# ads-b.net
KiCad netlist of a schematic drawn in EAGLE
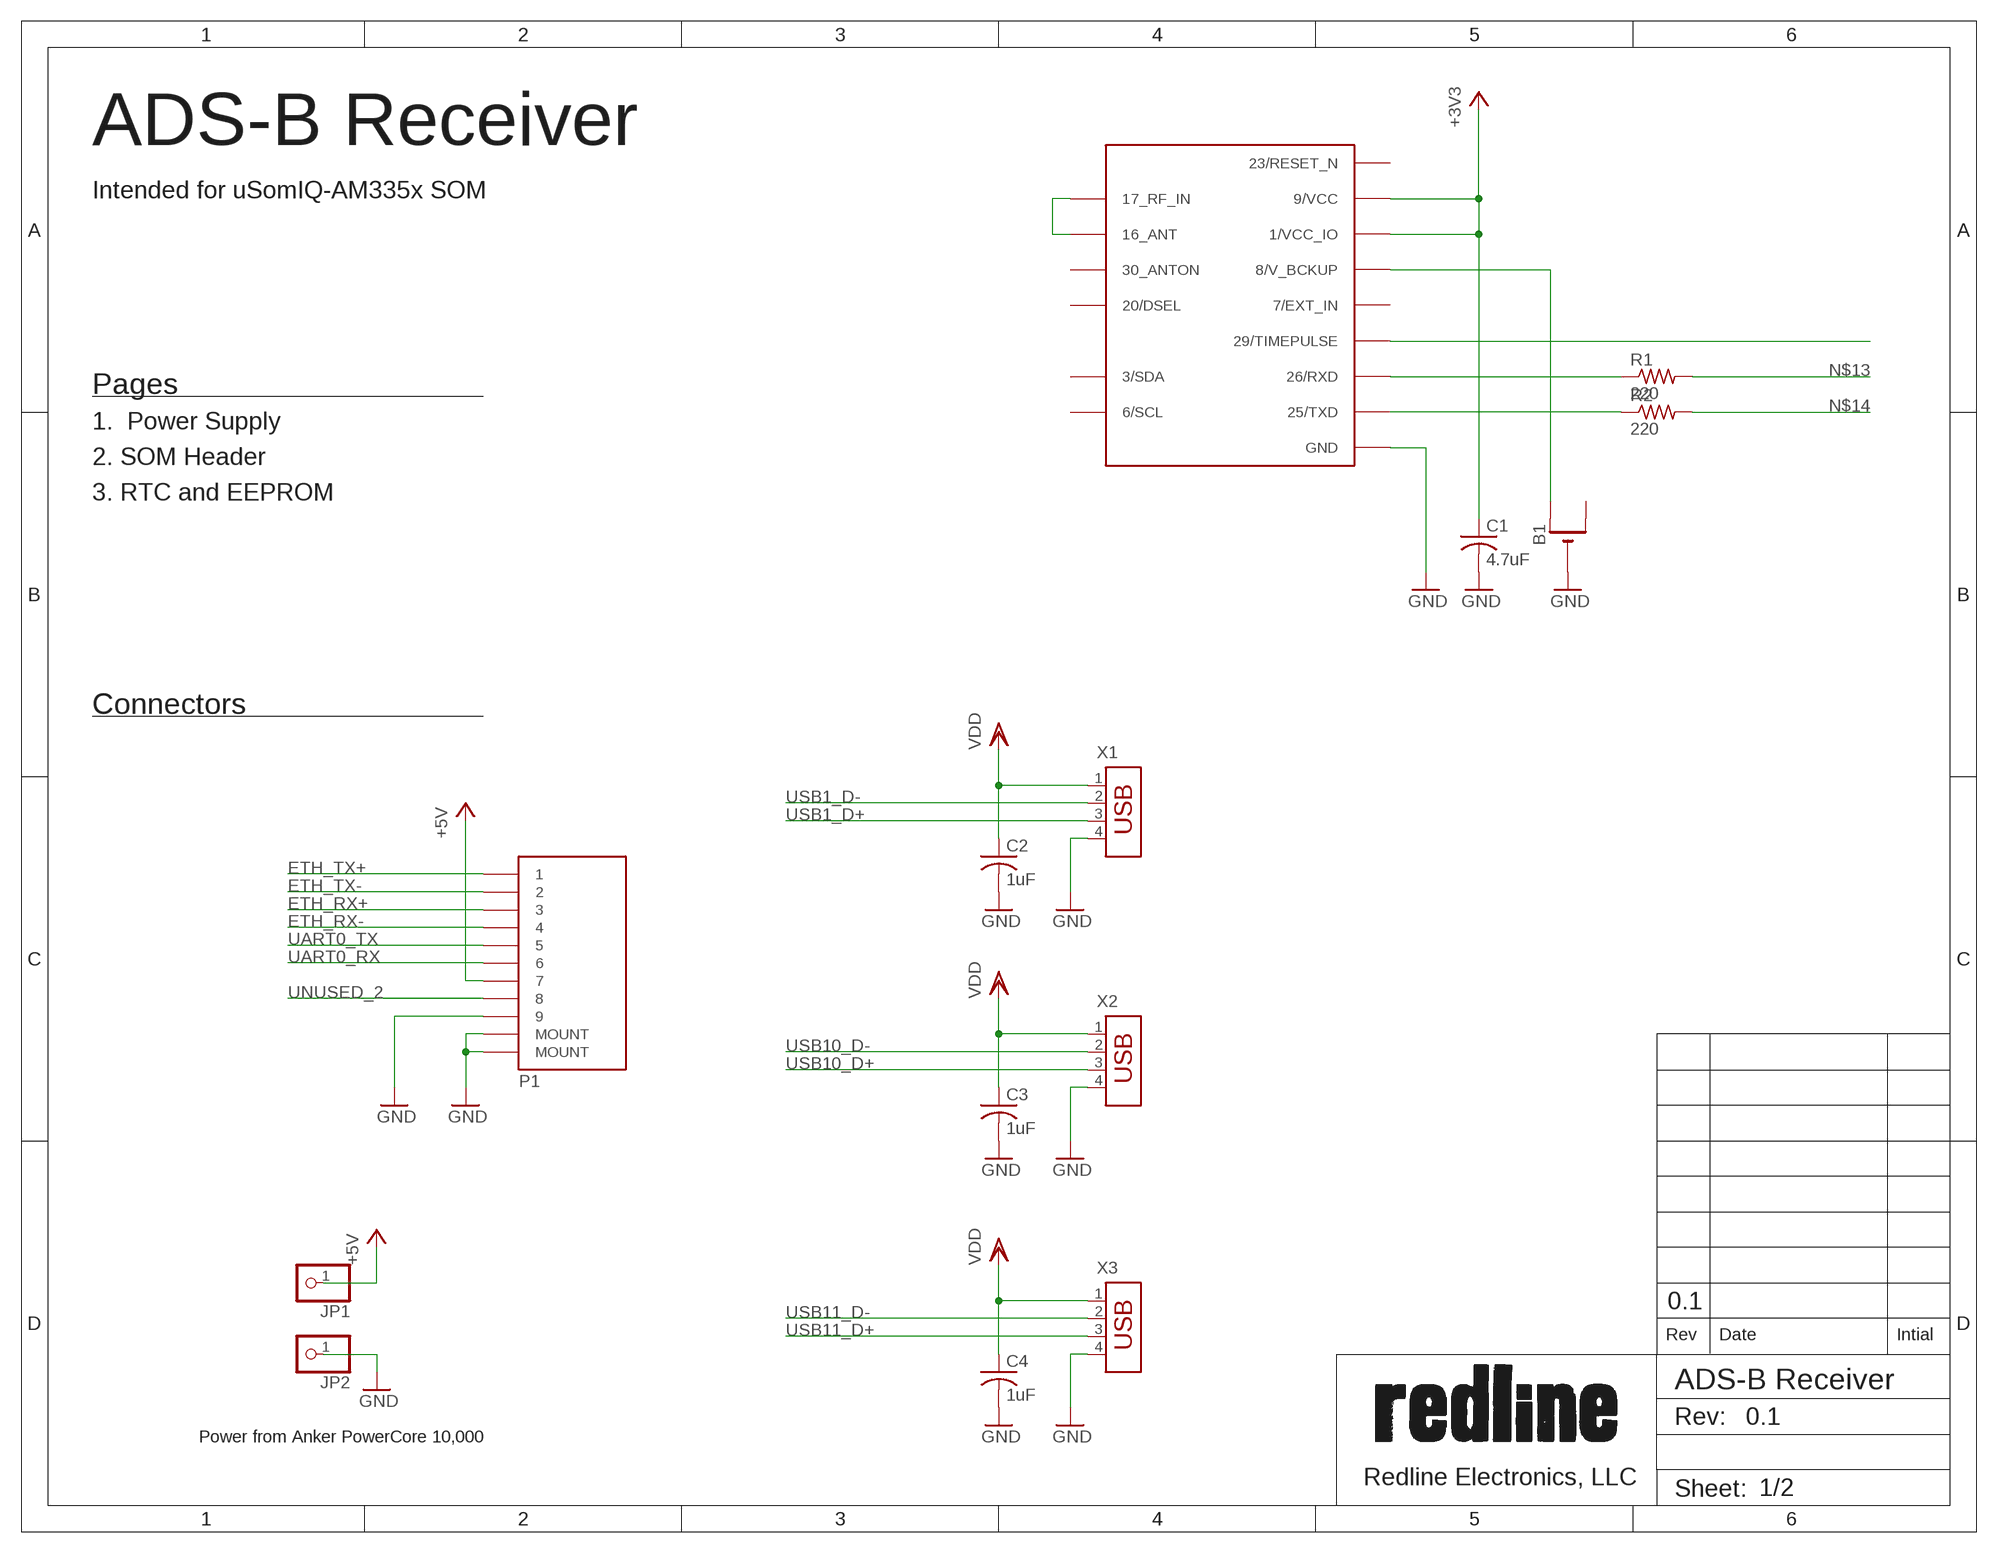
[diagram p0: schematic, sheet 1]
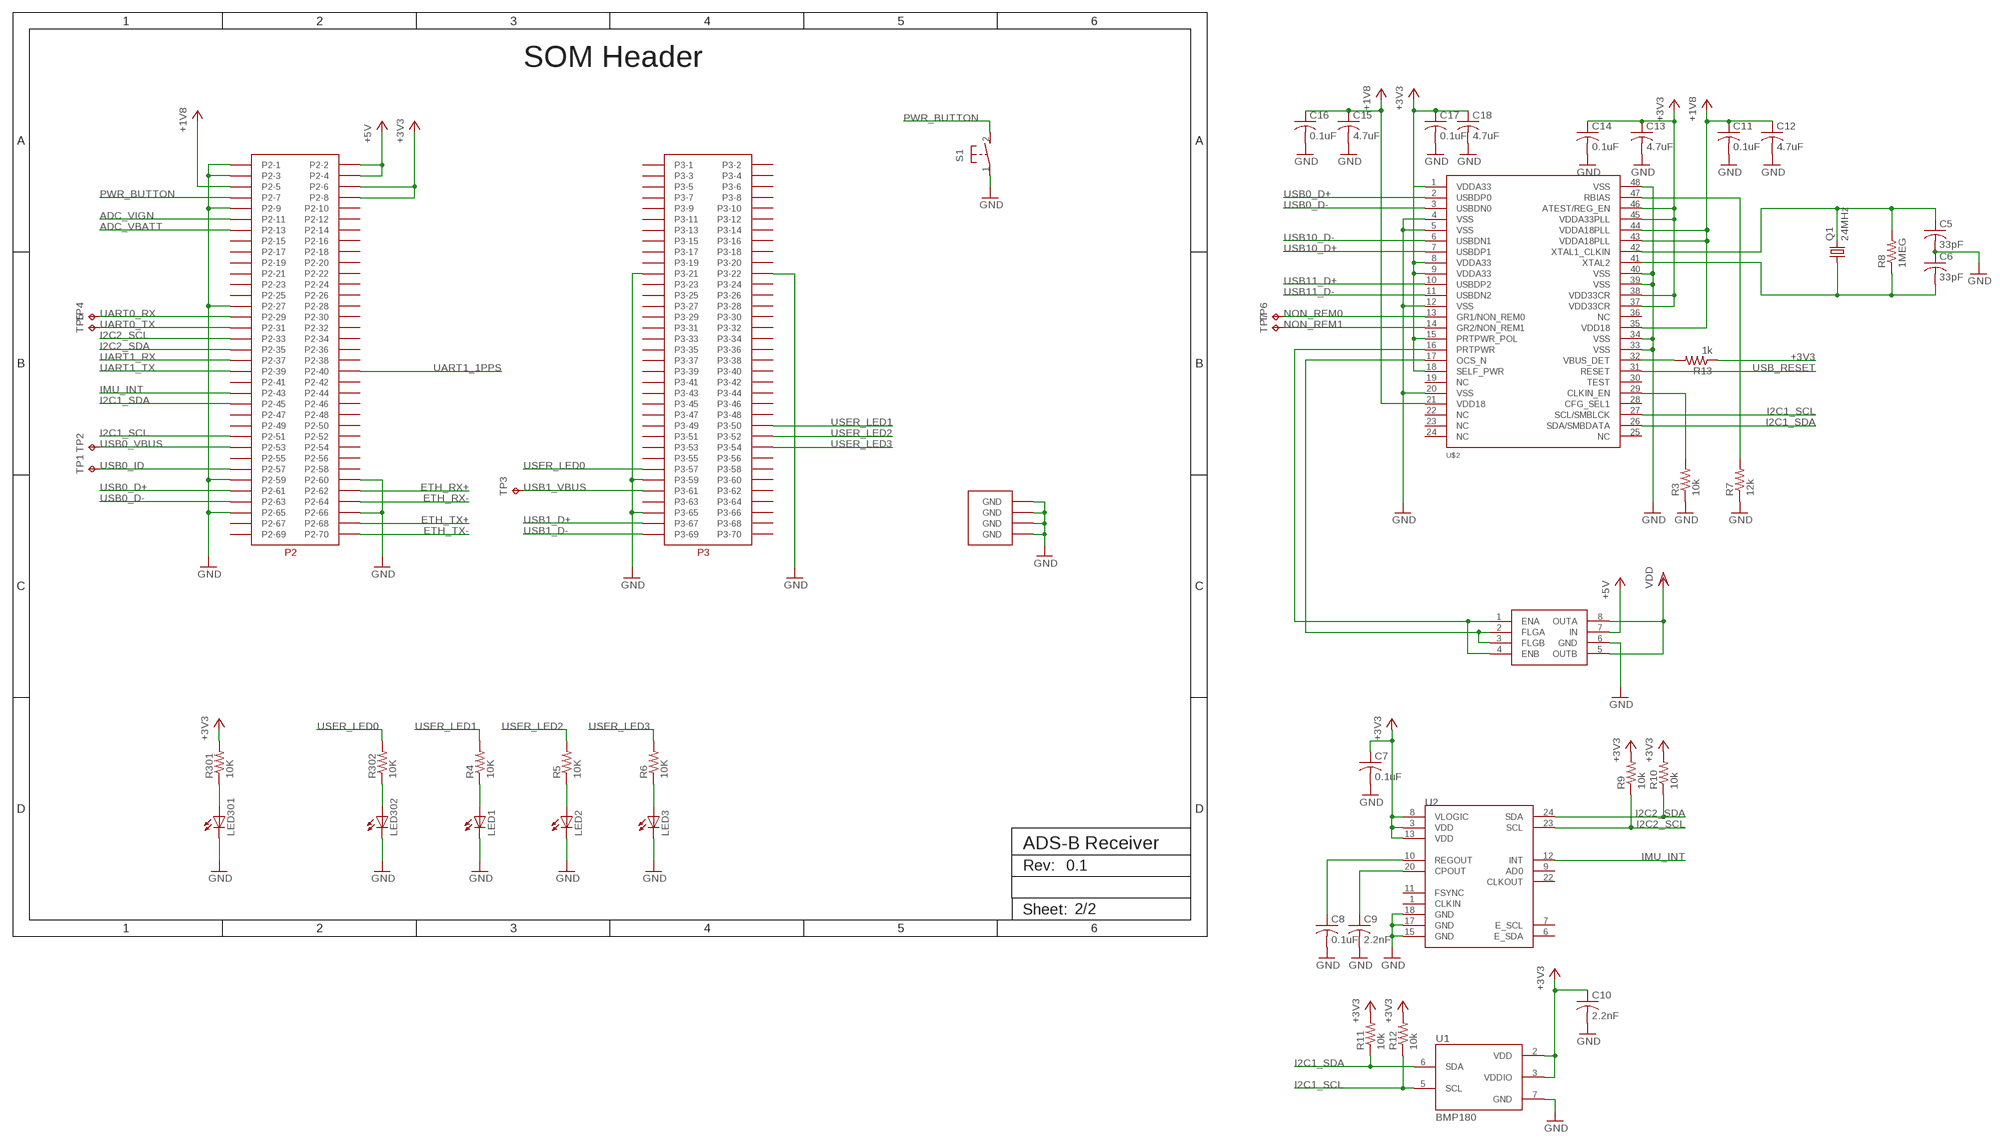
[diagram p1: schematic, sheet 2]

(export (version "E")
  (design (tool "Eeschema 10.0.6"))
  (components
    (comp (ref "C5")
      (value "33pF")
      (footprint "eagle-import:C0603")
      (libsource (lib "eagle-import") (part "C-USC0603"))
    )
    (comp (ref "C6")
      (value "33pF")
      (footprint "eagle-import:C0603")
      (libsource (lib "eagle-import") (part "C-USC0603"))
    )
    (comp (ref "C7")
      (value "0.1uF")
      (footprint "eagle-import:C0603")
      (libsource (lib "eagle-import") (part "C-USC0603"))
    )
    (comp (ref "C8")
      (value "0.1uF")
      (footprint "eagle-import:C0603")
      (libsource (lib "eagle-import") (part "C-USC0603"))
    )
    (comp (ref "C9")
      (value "2.2nF")
      (footprint "eagle-import:C0603")
      (libsource (lib "eagle-import") (part "C-USC0603"))
    )
    (comp (ref "C10")
      (value "2.2nF")
      (footprint "eagle-import:C0603")
      (libsource (lib "eagle-import") (part "C-USC0603"))
    )
    (comp (ref "C11")
      (value "0.1uF")
      (footprint "eagle-import:C0603")
      (libsource (lib "eagle-import") (part "C-USC0603"))
    )
    (comp (ref "C12")
      (value "4.7uF")
      (footprint "eagle-import:C0603")
      (libsource (lib "eagle-import") (part "C-USC0603"))
    )
    (comp (ref "C13")
      (value "4.7uF")
      (footprint "eagle-import:C0603")
      (libsource (lib "eagle-import") (part "C-USC0603"))
    )
    (comp (ref "C14")
      (value "0.1uF")
      (footprint "eagle-import:C0603")
      (libsource (lib "eagle-import") (part "C-USC0603"))
    )
    (comp (ref "C15")
      (value "4.7uF")
      (footprint "eagle-import:C0603")
      (libsource (lib "eagle-import") (part "C-USC0603"))
    )
    (comp (ref "C16")
      (value "0.1uF")
      (footprint "eagle-import:C0603")
      (libsource (lib "eagle-import") (part "C-USC0603"))
    )
    (comp (ref "C17")
      (value "0.1uF")
      (footprint "eagle-import:C0603")
      (libsource (lib "eagle-import") (part "C-USC0603"))
    )
    (comp (ref "C18")
      (value "4.7uF")
      (footprint "eagle-import:C0603")
      (libsource (lib "eagle-import") (part "C-USC0603"))
    )
    (comp (ref "LED1")
      (value "LEDSML0603")
      (footprint "eagle-import:SML0603")
      (libsource (lib "eagle-import") (part "LEDSML0603"))
    )
    (comp (ref "LED2")
      (value "LEDSML0603")
      (footprint "eagle-import:SML0603")
      (libsource (lib "eagle-import") (part "LEDSML0603"))
    )
    (comp (ref "LED3")
      (value "LEDSML0603")
      (footprint "eagle-import:SML0603")
      (libsource (lib "eagle-import") (part "LEDSML0603"))
    )
    (comp (ref "LED301")
      (value "LEDSML0603")
      (footprint "eagle-import:SML0603")
      (libsource (lib "eagle-import") (part "LEDSML0603"))
    )
    (comp (ref "LED302")
      (value "LEDSML0603")
      (footprint "eagle-import:SML0603")
      (libsource (lib "eagle-import") (part "LEDSML0603"))
    )
    (comp (ref "P301")
      (value "USOMIQ-AM335X")
      (footprint "eagle-import:USOMIQ-AM335X")
      (libsource (lib "eagle-import") (part "USOMIQ-AM335X"))
    )
    (comp (ref "Q1")
      (value "24MHz")
      (footprint "eagle-import:HC49_S")
      (libsource (lib "eagle-import") (part "CRYSTALHC49S"))
    )
    (comp (ref "R3")
      (value "10k")
      (footprint "eagle-import:R0603")
      (libsource (lib "eagle-import") (part "R-US_R0603"))
    )
    (comp (ref "R4")
      (value "10K")
      (footprint "eagle-import:R0603")
      (libsource (lib "eagle-import") (part "R-US_R0603"))
    )
    (comp (ref "R5")
      (value "10K")
      (footprint "eagle-import:R0603")
      (libsource (lib "eagle-import") (part "R-US_R0603"))
    )
    (comp (ref "R6")
      (value "10K")
      (footprint "eagle-import:R0603")
      (libsource (lib "eagle-import") (part "R-US_R0603"))
    )
    (comp (ref "R7")
      (value "12k")
      (footprint "eagle-import:R0603")
      (libsource (lib "eagle-import") (part "R-US_R0603"))
    )
    (comp (ref "R8")
      (value "1MEG")
      (footprint "eagle-import:R0603")
      (libsource (lib "eagle-import") (part "R-US_R0603"))
    )
    (comp (ref "R9")
      (value "10k")
      (footprint "eagle-import:R0603")
      (libsource (lib "eagle-import") (part "R-US_R0603"))
    )
    (comp (ref "R10")
      (value "10k")
      (footprint "eagle-import:R0603")
      (libsource (lib "eagle-import") (part "R-US_R0603"))
    )
    (comp (ref "R11")
      (value "10k")
      (footprint "eagle-import:R0603")
      (libsource (lib "eagle-import") (part "R-US_R0603"))
    )
    (comp (ref "R12")
      (value "10k")
      (footprint "eagle-import:R0603")
      (libsource (lib "eagle-import") (part "R-US_R0603"))
    )
    (comp (ref "R13")
      (value "1k")
      (footprint "eagle-import:R0603")
      (libsource (lib "eagle-import") (part "R-US_R0603"))
    )
    (comp (ref "R301")
      (value "10K")
      (footprint "eagle-import:R0603")
      (libsource (lib "eagle-import") (part "R-US_R0603"))
    )
    (comp (ref "R302")
      (value "10K")
      (footprint "eagle-import:R0603")
      (libsource (lib "eagle-import") (part "R-US_R0603"))
    )
    (comp (ref "S1")
      (value "31-XX")
      (footprint "eagle-import:B3F-31XX")
      (libsource (lib "eagle-import") (part "31-XX"))
    )
    (comp (ref "TP1")
      (value "TPB1,27")
      (footprint "eagle-import:B1,27")
      (libsource (lib "eagle-import") (part "TPB1,27"))
    )
    (comp (ref "TP2")
      (value "TPB1,27")
      (footprint "eagle-import:B1,27")
      (libsource (lib "eagle-import") (part "TPB1,27"))
    )
    (comp (ref "TP3")
      (value "TPB1,27")
      (footprint "eagle-import:B1,27")
      (libsource (lib "eagle-import") (part "TPB1,27"))
    )
    (comp (ref "TP4")
      (value "TPB1,27")
      (footprint "eagle-import:B1,27")
      (libsource (lib "eagle-import") (part "TPB1,27"))
    )
    (comp (ref "TP5")
      (value "TPB1,27")
      (footprint "eagle-import:B1,27")
      (libsource (lib "eagle-import") (part "TPB1,27"))
    )
    (comp (ref "TP6")
      (value "TPB1,27")
      (footprint "eagle-import:B1,27")
      (libsource (lib "eagle-import") (part "TPB1,27"))
    )
    (comp (ref "TP7")
      (value "TPB1,27")
      (footprint "eagle-import:B1,27")
      (libsource (lib "eagle-import") (part "TPB1,27"))
    )
    (comp (ref "U$2")
      (value "USB2502")
      (footprint "eagle-import:S-PQFP-G48")
      (libsource (lib "eagle-import") (part "USB2502"))
    )
    (comp (ref "U$3")
      (value "MIC2026")
      (footprint "eagle-import:SO8")
      (libsource (lib "eagle-import") (part "MIC2026"))
    )
    (comp (ref "U1")
      (value "BMP180")
      (footprint "eagle-import:BMP180")
      (libsource (lib "eagle-import") (part "BMP180"))
    )
    (comp (ref "U2")
      (value "MPU-9150QFN-24-NP")
      (footprint "eagle-import:QFN-24-NP")
      (libsource (lib "eagle-import") (part "MPU-9150QFN-24-NP"))
    )
    (comp (ref "B1")
      (value "CR1220THM")
      (footprint "eagle-import:CR1220-THM")
      (libsource (lib "eagle-import") (part "CR1220THM"))
    )
    (comp (ref "C1")
      (value "4.7uF")
      (footprint "eagle-import:C0603")
      (libsource (lib "eagle-import") (part "C-USC0603"))
    )
    (comp (ref "C2")
      (value "1uF")
      (footprint "eagle-import:C0603")
      (libsource (lib "eagle-import") (part "C-USC0603"))
    )
    (comp (ref "C3")
      (value "1uF")
      (footprint "eagle-import:C0603")
      (libsource (lib "eagle-import") (part "C-USC0603"))
    )
    (comp (ref "C4")
      (value "1uF")
      (footprint "eagle-import:C0603")
      (libsource (lib "eagle-import") (part "C-USC0603"))
    )
    (comp (ref "JP1")
      (value "PINHD-1X1")
      (footprint "eagle-import:1X01")
      (libsource (lib "eagle-import") (part "PINHD-1X1"))
    )
    (comp (ref "JP2")
      (value "PINHD-1X1")
      (footprint "eagle-import:1X01")
      (libsource (lib "eagle-import") (part "PINHD-1X1"))
    )
    (comp (ref "P1")
      (value "83611-9006")
      (footprint "eagle-import:83611-9006")
      (libsource (lib "eagle-import") (part "83611-9006"))
    )
    (comp (ref "R1")
      (value "220")
      (footprint "eagle-import:R0603")
      (libsource (lib "eagle-import") (part "R-US_R0603"))
    )
    (comp (ref "R2")
      (value "220")
      (footprint "eagle-import:R0603")
      (libsource (lib "eagle-import") (part "R-US_R0603"))
    )
    (comp (ref "U$1")
      (value "UBLOX_CAM")
      (footprint "eagle-import:UBLOX_CAM")
      (libsource (lib "eagle-import") (part "UBLOX_CAM"))
    )
    (comp (ref "X1")
      (value "USB-787616")
      (footprint "eagle-import:USB")
      (libsource (lib "eagle-import") (part "USB-787616"))
    )
    (comp (ref "X2")
      (value "USB-787616")
      (footprint "eagle-import:USB")
      (libsource (lib "eagle-import") (part "USB-787616"))
    )
    (comp (ref "X3")
      (value "USB-787616")
      (footprint "eagle-import:USB")
      (libsource (lib "eagle-import") (part "USB-787616"))
    )
  )
  (nets
    (net (code "1") (name "+3V3") (class "Default")
      (node (ref "C1") (pin "1") (pinfunction "1_1") (pintype "passive"))
      (node (ref "C10") (pin "1") (pinfunction "1_1") (pintype "passive"))
      (node (ref "C11") (pin "1") (pinfunction "1_1") (pintype "passive"))
      (node (ref "C12") (pin "1") (pinfunction "1_1") (pintype "passive"))
      (node (ref "C13") (pin "1") (pinfunction "1_1") (pintype "passive"))
      (node (ref "C14") (pin "1") (pinfunction "1_1") (pintype "passive"))
      (node (ref "C15") (pin "1") (pinfunction "1_1") (pintype "passive"))
      (node (ref "C16") (pin "1") (pinfunction "1_1") (pintype "passive"))
      (node (ref "C17") (pin "1") (pinfunction "1_1") (pintype "passive"))
      (node (ref "C18") (pin "1") (pinfunction "1_1") (pintype "passive"))
      (node (ref "C7") (pin "1") (pinfunction "1_1") (pintype "passive"))
      (node (ref "P301") (pin "P$5") (pinfunction "P2-5_P$5") (pintype "bidirectional"))
      (node (ref "P301") (pin "P$6") (pinfunction "P2-6_P$6") (pintype "bidirectional"))
      (node (ref "P301") (pin "P$8") (pinfunction "P2-8_P$8") (pintype "bidirectional"))
      (node (ref "R10") (pin "2") (pinfunction "2_2") (pintype "passive"))
      (node (ref "R11") (pin "2") (pinfunction "2_2") (pintype "passive"))
      (node (ref "R12") (pin "2") (pinfunction "2_2") (pintype "passive"))
      (node (ref "R13") (pin "1") (pinfunction "1_1") (pintype "passive"))
      (node (ref "R301") (pin "2") (pinfunction "2_2") (pintype "passive"))
      (node (ref "R9") (pin "2") (pinfunction "2_2") (pintype "passive"))
      (node (ref "U$1") (pin "1/VCC_IO") (pinfunction "1/VCC_IO_1/VCC_IO") (pintype "power_in"))
      (node (ref "U$1") (pin "9/VCC") (pinfunction "9/VCC_9/VCC") (pintype "power_in"))
      (node (ref "U$2") (pin "1") (pinfunction "VDDA33_1") (pintype "bidirectional"))
      (node (ref "U$2") (pin "15") (pinfunction "PRTPWR_POL_15") (pintype "bidirectional"))
      (node (ref "U$2") (pin "18") (pinfunction "SELF_PWR_18") (pintype "bidirectional"))
      (node (ref "U$2") (pin "21") (pinfunction "VDD18_21") (pintype "bidirectional"))
      (node (ref "U$2") (pin "35") (pinfunction "VDD18_35") (pintype "bidirectional"))
      (node (ref "U$2") (pin "37") (pinfunction "VDD33CR_37") (pintype "bidirectional"))
      (node (ref "U$2") (pin "38") (pinfunction "VDD33CR_38") (pintype "bidirectional"))
      (node (ref "U$2") (pin "43") (pinfunction "VDDA18PLL_43") (pintype "bidirectional"))
      (node (ref "U$2") (pin "44") (pinfunction "VDDA18PLL_44") (pintype "bidirectional"))
      (node (ref "U$2") (pin "45") (pinfunction "VDDA33PLL_45") (pintype "bidirectional"))
      (node (ref "U$2") (pin "46") (pinfunction "ATEST/REG_EN_46") (pintype "bidirectional"))
      (node (ref "U$2") (pin "8") (pinfunction "VDDA33_8") (pintype "bidirectional"))
      (node (ref "U$2") (pin "9") (pinfunction "VDDA33_9") (pintype "bidirectional"))
      (node (ref "U1") (pin "2") (pinfunction "VDD_2") (pintype "power_in"))
      (node (ref "U1") (pin "3") (pinfunction "VDDIO_3") (pintype "power_in"))
      (node (ref "U2") (pin "13") (pinfunction "VDD_13") (pintype "bidirectional"))
      (node (ref "U2") (pin "3") (pinfunction "VDD_3") (pintype "bidirectional"))
      (node (ref "U2") (pin "8") (pinfunction "VLOGIC_8") (pintype "bidirectional"))
    )
    (net (code "2") (name "+5V") (class "Default")
      (node (ref "JP1") (pin "1") (pinfunction "1_1") (pintype "passive"))
      (node (ref "P1") (pin "7") (pinfunction "7_7") (pintype "bidirectional"))
      (node (ref "P301") (pin "P$2") (pinfunction "P2-2_P$2") (pintype "bidirectional"))
      (node (ref "P301") (pin "P$4") (pinfunction "P2-4_P$4") (pintype "bidirectional"))
      (node (ref "U$3") (pin "7") (pinfunction "IN_7") (pintype "bidirectional"))
    )
    (net (code "3") (name "23{slash}RESET_N") (class "Default")
      (node (ref "U$1") (pin "23/RESET_N") (pinfunction "23/RESET_N_23/RESET_N") (pintype "power_in"))
    )
    (net (code "4") (name "ADC_VBATT") (class "Default")
      (node (ref "P301") (pin "P$13") (pinfunction "P2-13_P$13") (pintype "bidirectional"))
    )
    (net (code "5") (name "ADC_VIGN") (class "Default")
      (node (ref "P301") (pin "P$11") (pinfunction "P2-11_P$11") (pintype "bidirectional"))
    )
    (net (code "6") (name "ETH_RX+") (class "Default")
      (node (ref "P1") (pin "3") (pinfunction "3_3") (pintype "bidirectional"))
      (node (ref "P301") (pin "P$62") (pinfunction "P2-62_P$62") (pintype "bidirectional"))
    )
    (net (code "7") (name "ETH_RX-") (class "Default")
      (node (ref "P1") (pin "4") (pinfunction "4_4") (pintype "bidirectional"))
      (node (ref "P301") (pin "P$64") (pinfunction "P2-64_P$64") (pintype "bidirectional"))
    )
    (net (code "8") (name "ETH_TX+") (class "Default")
      (node (ref "P1") (pin "1") (pinfunction "1_1") (pintype "bidirectional"))
      (node (ref "P301") (pin "P$68") (pinfunction "P2-68_P$68") (pintype "bidirectional"))
    )
    (net (code "9") (name "ETH_TX-") (class "Default")
      (node (ref "P1") (pin "2") (pinfunction "2_2") (pintype "bidirectional"))
      (node (ref "P301") (pin "P$70") (pinfunction "P2-70_P$70") (pintype "bidirectional"))
    )
    (net (code "10") (name "GND") (class "Default")
      (node (ref "B1") (pin "-") (pinfunction "-_-") (pintype "passive"))
      (node (ref "C1") (pin "2") (pinfunction "2_2") (pintype "passive"))
      (node (ref "C10") (pin "2") (pinfunction "2_2") (pintype "passive"))
      (node (ref "C11") (pin "2") (pinfunction "2_2") (pintype "passive"))
      (node (ref "C12") (pin "2") (pinfunction "2_2") (pintype "passive"))
      (node (ref "C13") (pin "2") (pinfunction "2_2") (pintype "passive"))
      (node (ref "C14") (pin "2") (pinfunction "2_2") (pintype "passive"))
      (node (ref "C15") (pin "2") (pinfunction "2_2") (pintype "passive"))
      (node (ref "C16") (pin "2") (pinfunction "2_2") (pintype "passive"))
      (node (ref "C17") (pin "2") (pinfunction "2_2") (pintype "passive"))
      (node (ref "C18") (pin "2") (pinfunction "2_2") (pintype "passive"))
      (node (ref "C2") (pin "2") (pinfunction "2_2") (pintype "passive"))
      (node (ref "C3") (pin "2") (pinfunction "2_2") (pintype "passive"))
      (node (ref "C4") (pin "2") (pinfunction "2_2") (pintype "passive"))
      (node (ref "C5") (pin "2") (pinfunction "2_2") (pintype "passive"))
      (node (ref "C6") (pin "1") (pinfunction "1_1") (pintype "passive"))
      (node (ref "C7") (pin "2") (pinfunction "2_2") (pintype "passive"))
      (node (ref "C8") (pin "2") (pinfunction "2_2") (pintype "passive"))
      (node (ref "C9") (pin "2") (pinfunction "2_2") (pintype "passive"))
      (node (ref "JP2") (pin "1") (pinfunction "1_1") (pintype "passive"))
      (node (ref "LED1") (pin "C") (pinfunction "C_C") (pintype "passive"))
      (node (ref "LED2") (pin "C") (pinfunction "C_C") (pintype "passive"))
      (node (ref "LED3") (pin "C") (pinfunction "C_C") (pintype "passive"))
      (node (ref "LED301") (pin "C") (pinfunction "C_C") (pintype "passive"))
      (node (ref "LED302") (pin "C") (pinfunction "C_C") (pintype "passive"))
      (node (ref "P1") (pin "9") (pinfunction "9_9") (pintype "bidirectional"))
      (node (ref "P1") (pin "MOUNT@1") (pinfunction "MOUNT_MOUNT@1") (pintype "bidirectional"))
      (node (ref "P1") (pin "MOUNT@2") (pinfunction "MOUNT_MOUNT@2") (pintype "bidirectional"))
      (node (ref "P301") (pin "MOUNT@0") (pinfunction "GND_MOUNT@0") (pintype "bidirectional"))
      (node (ref "P301") (pin "MOUNT@1") (pinfunction "GND_MOUNT@1") (pintype "bidirectional"))
      (node (ref "P301") (pin "MOUNT@2") (pinfunction "GND_MOUNT@2") (pintype "bidirectional"))
      (node (ref "P301") (pin "MOUNT@3") (pinfunction "GND_MOUNT@3") (pintype "bidirectional"))
      (node (ref "P301") (pin "P$1") (pinfunction "P2-1_P$1") (pintype "bidirectional"))
      (node (ref "P301") (pin "P$129") (pinfunction "P3-59_P$129") (pintype "bidirectional"))
      (node (ref "P301") (pin "P$135") (pinfunction "P3-65_P$135") (pintype "bidirectional"))
      (node (ref "P301") (pin "P$27") (pinfunction "P2-27_P$27") (pintype "bidirectional"))
      (node (ref "P301") (pin "P$3") (pinfunction "P2-3_P$3") (pintype "bidirectional"))
      (node (ref "P301") (pin "P$59") (pinfunction "P2-59_P$59") (pintype "bidirectional"))
      (node (ref "P301") (pin "P$60") (pinfunction "P2-60_P$60") (pintype "bidirectional"))
      (node (ref "P301") (pin "P$65") (pinfunction "P2-65_P$65") (pintype "bidirectional"))
      (node (ref "P301") (pin "P$66") (pinfunction "P2-66_P$66") (pintype "bidirectional"))
      (node (ref "P301") (pin "P$9") (pinfunction "P2-9_P$9") (pintype "bidirectional"))
      (node (ref "P301") (pin "P$91") (pinfunction "P3-21_P$91") (pintype "bidirectional"))
      (node (ref "P301") (pin "P$92") (pinfunction "P3-22_P$92") (pintype "bidirectional"))
      (node (ref "R3") (pin "1") (pinfunction "1_1") (pintype "passive"))
      (node (ref "R7") (pin "1") (pinfunction "1_1") (pintype "passive"))
      (node (ref "S1") (pin "1") (pinfunction "P_1") (pintype "passive"))
      (node (ref "U$1") (pin "10/GND") (pinfunction "GND_10/GND") (pintype "power_in"))
      (node (ref "U$1") (pin "11/GND") (pinfunction "GND_11/GND") (pintype "power_in"))
      (node (ref "U$1") (pin "12/GND") (pinfunction "GND_12/GND") (pintype "power_in"))
      (node (ref "U$1") (pin "13/GND") (pinfunction "GND_13/GND") (pintype "power_in"))
      (node (ref "U$1") (pin "14/GND") (pinfunction "GND_14/GND") (pintype "power_in"))
      (node (ref "U$1") (pin "15/GND") (pinfunction "GND_15/GND") (pintype "power_in"))
      (node (ref "U$1") (pin "18/GND") (pinfunction "GND_18/GND") (pintype "power_in"))
      (node (ref "U$1") (pin "19/GND") (pinfunction "GND_19/GND") (pintype "power_in"))
      (node (ref "U$1") (pin "21/GND") (pinfunction "GND_21/GND") (pintype "power_in"))
      (node (ref "U$1") (pin "22/GND") (pinfunction "GND_22/GND") (pintype "power_in"))
      (node (ref "U$1") (pin "27/GND") (pinfunction "GND_27/GND") (pintype "power_in"))
      (node (ref "U$1") (pin "31/GND") (pinfunction "GND_31/GND") (pintype "power_in"))
      (node (ref "U$1") (pin "4/GND") (pinfunction "GND_4/GND") (pintype "power_in"))
      (node (ref "U$1") (pin "5/GND") (pinfunction "GND_5/GND") (pintype "power_in"))
      (node (ref "U$2") (pin "12") (pinfunction "VSS_12") (pintype "bidirectional"))
      (node (ref "U$2") (pin "20") (pinfunction "VSS_20") (pintype "bidirectional"))
      (node (ref "U$2") (pin "33") (pinfunction "VSS_33") (pintype "bidirectional"))
      (node (ref "U$2") (pin "34") (pinfunction "VSS_34") (pintype "bidirectional"))
      (node (ref "U$2") (pin "39") (pinfunction "VSS_39") (pintype "bidirectional"))
      (node (ref "U$2") (pin "4") (pinfunction "VSS_4") (pintype "bidirectional"))
      (node (ref "U$2") (pin "40") (pinfunction "VSS_40") (pintype "bidirectional"))
      (node (ref "U$2") (pin "48") (pinfunction "VSS_48") (pintype "bidirectional"))
      (node (ref "U$2") (pin "5") (pinfunction "VSS_5") (pintype "bidirectional"))
      (node (ref "U$3") (pin "6") (pinfunction "GND_6") (pintype "bidirectional"))
      (node (ref "U1") (pin "7") (pinfunction "GND_7") (pintype "power_in"))
      (node (ref "U2") (pin "15") (pinfunction "GND_15") (pintype "bidirectional"))
      (node (ref "U2") (pin "17") (pinfunction "GND_17") (pintype "bidirectional"))
      (node (ref "U2") (pin "18") (pinfunction "GND_18") (pintype "bidirectional"))
      (node (ref "X1") (pin "4") (pinfunction "4_4") (pintype "passive"))
      (node (ref "X2") (pin "4") (pinfunction "4_4") (pintype "passive"))
      (node (ref "X3") (pin "4") (pinfunction "4_4") (pintype "passive"))
    )
    (net (code "11") (name "I2C1_SCL") (class "Default")
      (node (ref "P301") (pin "P$51") (pinfunction "P2-51_P$51") (pintype "bidirectional"))
      (node (ref "R12") (pin "1") (pinfunction "1_1") (pintype "passive"))
      (node (ref "U$2") (pin "27") (pinfunction "SCL/SMBLCK_27") (pintype "bidirectional"))
      (node (ref "U1") (pin "5") (pinfunction "SCL_5") (pintype "input"))
    )
    (net (code "12") (name "I2C1_SDA") (class "Default")
      (node (ref "P301") (pin "P$45") (pinfunction "P2-45_P$45") (pintype "bidirectional"))
      (node (ref "R11") (pin "1") (pinfunction "1_1") (pintype "passive"))
      (node (ref "U$2") (pin "26") (pinfunction "SDA/SMBDATA_26") (pintype "bidirectional"))
      (node (ref "U1") (pin "6") (pinfunction "SDA_6") (pintype "bidirectional"))
    )
    (net (code "13") (name "I2C2_SCL") (class "Default")
      (node (ref "P301") (pin "P$33") (pinfunction "P2-33_P$33") (pintype "bidirectional"))
      (node (ref "R9") (pin "1") (pinfunction "1_1") (pintype "passive"))
      (node (ref "U2") (pin "23") (pinfunction "SCL_23") (pintype "bidirectional"))
    )
    (net (code "14") (name "I2C2_SDA") (class "Default")
      (node (ref "P301") (pin "P$35") (pinfunction "P2-35_P$35") (pintype "bidirectional"))
      (node (ref "R10") (pin "1") (pinfunction "1_1") (pintype "passive"))
      (node (ref "U2") (pin "24") (pinfunction "SDA_24") (pintype "bidirectional"))
    )
    (net (code "15") (name "IMU_INT") (class "Default")
      (node (ref "P301") (pin "P$43") (pinfunction "P2-43_P$43") (pintype "bidirectional"))
      (node (ref "U2") (pin "12") (pinfunction "INT_12") (pintype "bidirectional"))
    )
    (net (code "16") (name "N$13") (class "Default")
      (node (ref "R1") (pin "2") (pinfunction "2_2") (pintype "passive"))
    )
    (net (code "17") (name "N$14") (class "Default")
      (node (ref "R2") (pin "2") (pinfunction "2_2") (pintype "passive"))
    )
    (net (code "18") (name "NON_REM0") (class "Default")
      (node (ref "TP6") (pin "TP") (pinfunction "TP_TP") (pintype "input"))
      (node (ref "U$2") (pin "13") (pinfunction "GR1/NON_REM0_13") (pintype "bidirectional"))
    )
    (net (code "19") (name "NON_REM1") (class "Default")
      (node (ref "TP7") (pin "TP") (pinfunction "TP_TP") (pintype "input"))
      (node (ref "U$2") (pin "14") (pinfunction "GR2/NON_REM1_14") (pintype "bidirectional"))
    )
    (net (code "20") (name "Net-(B1-+)") (class "Default")
      (node (ref "B1") (pin "+1") (pinfunction "+_+1") (pintype "passive"))
      (node (ref "U$1") (pin "8/V_BCKP") (pinfunction "8/V_BCKUP_8/V_BCKP") (pintype "bidirectional"))
    )
    (net (code "21") (name "Net-(LED1-PadA)") (class "Default")
      (node (ref "LED1") (pin "A") (pinfunction "A_A") (pintype "passive"))
      (node (ref "R4") (pin "1") (pinfunction "1_1") (pintype "passive"))
    )
    (net (code "22") (name "Net-(LED2-PadA)") (class "Default")
      (node (ref "LED2") (pin "A") (pinfunction "A_A") (pintype "passive"))
      (node (ref "R5") (pin "1") (pinfunction "1_1") (pintype "passive"))
    )
    (net (code "23") (name "Net-(LED3-PadA)") (class "Default")
      (node (ref "LED3") (pin "A") (pinfunction "A_A") (pintype "passive"))
      (node (ref "R6") (pin "1") (pinfunction "1_1") (pintype "passive"))
    )
    (net (code "24") (name "Net-(LED301-PadA)") (class "Default")
      (node (ref "LED301") (pin "A") (pinfunction "A_A") (pintype "passive"))
      (node (ref "R301") (pin "1") (pinfunction "1_1") (pintype "passive"))
    )
    (net (code "25") (name "Net-(LED302-PadA)") (class "Default")
      (node (ref "LED302") (pin "A") (pinfunction "A_A") (pintype "passive"))
      (node (ref "R302") (pin "1") (pinfunction "1_1") (pintype "passive"))
    )
    (net (code "26") (name "Net-(R1-Pad1)") (class "Default")
      (node (ref "R1") (pin "1") (pinfunction "1_1") (pintype "passive"))
      (node (ref "U$1") (pin "26/RXD") (pinfunction "26/RXD_26/RXD") (pintype "bidirectional"))
    )
    (net (code "27") (name "Net-(R2-Pad1)") (class "Default")
      (node (ref "R2") (pin "1") (pinfunction "1_1") (pintype "passive"))
      (node (ref "U$1") (pin "25/TXD") (pinfunction "25/TXD_25/TXD") (pintype "bidirectional"))
    )
    (net (code "28") (name "Net-(U$1-16_ANT)") (class "Default")
      (node (ref "U$1") (pin "16/ANT") (pinfunction "16_ANT_16/ANT") (pintype "power_in"))
      (node (ref "U$1") (pin "17/RF_IN") (pinfunction "17_RF_IN_17/RF_IN") (pintype "bidirectional"))
    )
    (net (code "29") (name "Net-(U$2-CLKIN_EN)") (class "Default")
      (node (ref "R3") (pin "2") (pinfunction "2_2") (pintype "passive"))
      (node (ref "U$2") (pin "29") (pinfunction "CLKIN_EN_29") (pintype "bidirectional"))
    )
    (net (code "30") (name "Net-(U$2-OCS_N)") (class "Default")
      (node (ref "U$2") (pin "17") (pinfunction "OCS_N_17") (pintype "bidirectional"))
      (node (ref "U$3") (pin "2") (pinfunction "FLGA_2") (pintype "bidirectional"))
      (node (ref "U$3") (pin "3") (pinfunction "FLGB_3") (pintype "bidirectional"))
    )
    (net (code "31") (name "Net-(U$2-PRTPWR)") (class "Default")
      (node (ref "U$2") (pin "16") (pinfunction "PRTPWR_16") (pintype "bidirectional"))
      (node (ref "U$3") (pin "1") (pinfunction "ENA_1") (pintype "bidirectional"))
      (node (ref "U$3") (pin "4") (pinfunction "ENB_4") (pintype "bidirectional"))
    )
    (net (code "32") (name "Net-(U$2-RBIAS)") (class "Default")
      (node (ref "R7") (pin "2") (pinfunction "2_2") (pintype "passive"))
      (node (ref "U$2") (pin "47") (pinfunction "RBIAS_47") (pintype "bidirectional"))
    )
    (net (code "33") (name "Net-(U$2-VBUS_DET)") (class "Default")
      (node (ref "R13") (pin "2") (pinfunction "2_2") (pintype "passive"))
      (node (ref "U$2") (pin "32") (pinfunction "VBUS_DET_32") (pintype "bidirectional"))
    )
    (net (code "34") (name "Net-(U$2-XTAL1_CLKIN)") (class "Default")
      (node (ref "C5") (pin "1") (pinfunction "1_1") (pintype "passive"))
      (node (ref "Q1") (pin "2") (pinfunction "2_2") (pintype "passive"))
      (node (ref "R8") (pin "2") (pinfunction "2_2") (pintype "passive"))
      (node (ref "U$2") (pin "42") (pinfunction "XTAL1_CLKIN_42") (pintype "bidirectional"))
    )
    (net (code "35") (name "Net-(U$2-XTAL2)") (class "Default")
      (node (ref "C6") (pin "2") (pinfunction "2_2") (pintype "passive"))
      (node (ref "Q1") (pin "1") (pinfunction "1_1") (pintype "passive"))
      (node (ref "R8") (pin "1") (pinfunction "1_1") (pintype "passive"))
      (node (ref "U$2") (pin "41") (pinfunction "XTAL2_41") (pintype "bidirectional"))
    )
    (net (code "36") (name "Net-(U2-CPOUT)") (class "Default")
      (node (ref "C9") (pin "1") (pinfunction "1_1") (pintype "passive"))
      (node (ref "U2") (pin "20") (pinfunction "CPOUT_20") (pintype "bidirectional"))
    )
    (net (code "37") (name "Net-(U2-REGOUT)") (class "Default")
      (node (ref "C8") (pin "1") (pinfunction "1_1") (pintype "passive"))
      (node (ref "U2") (pin "10") (pinfunction "REGOUT_10") (pintype "bidirectional"))
    )
    (net (code "38") (name "PWR_BUTTON") (class "Default")
      (node (ref "P301") (pin "P$7") (pinfunction "P2-7_P$7") (pintype "bidirectional"))
      (node (ref "S1") (pin "2") (pinfunction "S_2") (pintype "passive"))
    )
    (net (code "39") (name "UART0_RX") (class "Default")
      (node (ref "P1") (pin "6") (pinfunction "6_6") (pintype "bidirectional"))
      (node (ref "P301") (pin "P$29") (pinfunction "P2-29_P$29") (pintype "bidirectional"))
      (node (ref "TP4") (pin "TP") (pinfunction "TP_TP") (pintype "input"))
    )
    (net (code "40") (name "UART0_TX") (class "Default")
      (node (ref "P1") (pin "5") (pinfunction "5_5") (pintype "bidirectional"))
      (node (ref "P301") (pin "P$31") (pinfunction "P2-31_P$31") (pintype "bidirectional"))
      (node (ref "TP5") (pin "TP") (pinfunction "TP_TP") (pintype "input"))
    )
    (net (code "41") (name "UART1_1PPS") (class "Default")
      (node (ref "P301") (pin "P$40") (pinfunction "P2-40_P$40") (pintype "bidirectional"))
    )
    (net (code "42") (name "UART1_RX") (class "Default")
      (node (ref "P301") (pin "P$37") (pinfunction "P2-37_P$37") (pintype "bidirectional"))
    )
    (net (code "43") (name "UART1_TX") (class "Default")
      (node (ref "P301") (pin "P$39") (pinfunction "P2-39_P$39") (pintype "bidirectional"))
    )
    (net (code "44") (name "UNUSED_2") (class "Default")
      (node (ref "P1") (pin "8") (pinfunction "8_8") (pintype "bidirectional"))
    )
    (net (code "45") (name "USB0_D+") (class "Default")
      (node (ref "P301") (pin "P$61") (pinfunction "P2-61_P$61") (pintype "bidirectional"))
      (node (ref "U$2") (pin "2") (pinfunction "USBDP0_2") (pintype "bidirectional"))
    )
    (net (code "46") (name "USB0_D-") (class "Default")
      (node (ref "P301") (pin "P$63") (pinfunction "P2-63_P$63") (pintype "bidirectional"))
      (node (ref "U$2") (pin "3") (pinfunction "USBDN0_3") (pintype "bidirectional"))
    )
    (net (code "47") (name "USB0_ID") (class "Default")
      (node (ref "P301") (pin "P$57") (pinfunction "P2-57_P$57") (pintype "bidirectional"))
      (node (ref "TP1") (pin "TP") (pinfunction "TP_TP") (pintype "input"))
    )
    (net (code "48") (name "USB0_VBUS") (class "Default")
      (node (ref "P301") (pin "P$53") (pinfunction "P2-53_P$53") (pintype "bidirectional"))
      (node (ref "TP2") (pin "TP") (pinfunction "TP_TP") (pintype "input"))
    )
    (net (code "49") (name "USB1_D+") (class "Default")
      (node (ref "P301") (pin "P$137") (pinfunction "P3-67_P$137") (pintype "bidirectional"))
      (node (ref "X1") (pin "3") (pinfunction "3_3") (pintype "passive"))
    )
    (net (code "50") (name "USB1_D-") (class "Default")
      (node (ref "P301") (pin "P$139") (pinfunction "P3-69_P$139") (pintype "bidirectional"))
      (node (ref "X1") (pin "2") (pinfunction "2_2") (pintype "passive"))
    )
    (net (code "51") (name "USB1_VBUS") (class "Default")
      (node (ref "P301") (pin "P$131") (pinfunction "P3-61_P$131") (pintype "bidirectional"))
      (node (ref "TP3") (pin "TP") (pinfunction "TP_TP") (pintype "input"))
    )
    (net (code "52") (name "USB10_D+") (class "Default")
      (node (ref "U$2") (pin "7") (pinfunction "USBDP1_7") (pintype "bidirectional"))
      (node (ref "X2") (pin "3") (pinfunction "3_3") (pintype "passive"))
    )
    (net (code "53") (name "USB10_D-") (class "Default")
      (node (ref "U$2") (pin "6") (pinfunction "USBDN1_6") (pintype "bidirectional"))
      (node (ref "X2") (pin "2") (pinfunction "2_2") (pintype "passive"))
    )
    (net (code "54") (name "USB11_D+") (class "Default")
      (node (ref "U$2") (pin "10") (pinfunction "USBDP2_10") (pintype "bidirectional"))
      (node (ref "X3") (pin "3") (pinfunction "3_3") (pintype "passive"))
    )
    (net (code "55") (name "USB11_D-") (class "Default")
      (node (ref "U$2") (pin "11") (pinfunction "USBDN2_11") (pintype "bidirectional"))
      (node (ref "X3") (pin "2") (pinfunction "2_2") (pintype "passive"))
    )
    (net (code "56") (name "USB_RESET") (class "Default")
      (node (ref "U$2") (pin "31") (pinfunction "RESET_31") (pintype "bidirectional"))
    )
    (net (code "57") (name "USER_LED0") (class "Default")
      (node (ref "P301") (pin "P$127") (pinfunction "P3-57_P$127") (pintype "bidirectional"))
      (node (ref "R302") (pin "2") (pinfunction "2_2") (pintype "passive"))
    )
    (net (code "58") (name "USER_LED1") (class "Default")
      (node (ref "P301") (pin "P$120") (pinfunction "P3-50_P$120") (pintype "bidirectional"))
      (node (ref "R4") (pin "2") (pinfunction "2_2") (pintype "passive"))
    )
    (net (code "59") (name "USER_LED2") (class "Default")
      (node (ref "P301") (pin "P$122") (pinfunction "P3-52_P$122") (pintype "bidirectional"))
      (node (ref "R5") (pin "2") (pinfunction "2_2") (pintype "passive"))
    )
    (net (code "60") (name "USER_LED3") (class "Default")
      (node (ref "P301") (pin "P$124") (pinfunction "P3-54_P$124") (pintype "bidirectional"))
      (node (ref "R6") (pin "2") (pinfunction "2_2") (pintype "passive"))
    )
    (net (code "61") (name "VDD") (class "Default")
      (node (ref "C2") (pin "1") (pinfunction "1_1") (pintype "passive"))
      (node (ref "C3") (pin "1") (pinfunction "1_1") (pintype "passive"))
      (node (ref "C4") (pin "1") (pinfunction "1_1") (pintype "passive"))
      (node (ref "U$3") (pin "5") (pinfunction "OUTB_5") (pintype "bidirectional"))
      (node (ref "U$3") (pin "8") (pinfunction "OUTA_8") (pintype "bidirectional"))
      (node (ref "X1") (pin "1") (pinfunction "1_1") (pintype "passive"))
      (node (ref "X2") (pin "1") (pinfunction "1_1") (pintype "passive"))
      (node (ref "X3") (pin "1") (pinfunction "1_1") (pintype "passive"))
    )
    (net (code "62") (name "unconnected-(B1-+1-Pad+2)") (class "Default")
      (node (ref "B1") (pin "+2") (pinfunction "+1_+2") (pintype "passive"))
    )
    (net (code "63") (name "unconnected-(P301-P2-10-PadP$10)") (class "Default")
      (node (ref "P301") (pin "P$10") (pinfunction "P2-10_P$10") (pintype "bidirectional"))
    )
    (net (code "64") (name "unconnected-(P301-P2-12-PadP$12)") (class "Default")
      (node (ref "P301") (pin "P$12") (pinfunction "P2-12_P$12") (pintype "bidirectional"))
    )
    (net (code "65") (name "unconnected-(P301-P2-14-PadP$14)") (class "Default")
      (node (ref "P301") (pin "P$14") (pinfunction "P2-14_P$14") (pintype "bidirectional"))
    )
    (net (code "66") (name "unconnected-(P301-P2-15-PadP$15)") (class "Default")
      (node (ref "P301") (pin "P$15") (pinfunction "P2-15_P$15") (pintype "bidirectional"))
    )
    (net (code "67") (name "unconnected-(P301-P2-16-PadP$16)") (class "Default")
      (node (ref "P301") (pin "P$16") (pinfunction "P2-16_P$16") (pintype "bidirectional"))
    )
    (net (code "68") (name "unconnected-(P301-P2-17-PadP$17)") (class "Default")
      (node (ref "P301") (pin "P$17") (pinfunction "P2-17_P$17") (pintype "bidirectional"))
    )
    (net (code "69") (name "unconnected-(P301-P2-18-PadP$18)") (class "Default")
      (node (ref "P301") (pin "P$18") (pinfunction "P2-18_P$18") (pintype "bidirectional"))
    )
    (net (code "70") (name "unconnected-(P301-P2-19-PadP$19)") (class "Default")
      (node (ref "P301") (pin "P$19") (pinfunction "P2-19_P$19") (pintype "bidirectional"))
    )
    (net (code "71") (name "unconnected-(P301-P2-20-PadP$20)") (class "Default")
      (node (ref "P301") (pin "P$20") (pinfunction "P2-20_P$20") (pintype "bidirectional"))
    )
    (net (code "72") (name "unconnected-(P301-P2-21-PadP$21)") (class "Default")
      (node (ref "P301") (pin "P$21") (pinfunction "P2-21_P$21") (pintype "bidirectional"))
    )
    (net (code "73") (name "unconnected-(P301-P2-22-PadP$22)") (class "Default")
      (node (ref "P301") (pin "P$22") (pinfunction "P2-22_P$22") (pintype "bidirectional"))
    )
    (net (code "74") (name "unconnected-(P301-P2-23-PadP$23)") (class "Default")
      (node (ref "P301") (pin "P$23") (pinfunction "P2-23_P$23") (pintype "bidirectional"))
    )
    (net (code "75") (name "unconnected-(P301-P2-24-PadP$24)") (class "Default")
      (node (ref "P301") (pin "P$24") (pinfunction "P2-24_P$24") (pintype "bidirectional"))
    )
    (net (code "76") (name "unconnected-(P301-P2-25-PadP$25)") (class "Default")
      (node (ref "P301") (pin "P$25") (pinfunction "P2-25_P$25") (pintype "bidirectional"))
    )
    (net (code "77") (name "unconnected-(P301-P2-26-PadP$26)") (class "Default")
      (node (ref "P301") (pin "P$26") (pinfunction "P2-26_P$26") (pintype "bidirectional"))
    )
    (net (code "78") (name "unconnected-(P301-P2-28-PadP$28)") (class "Default")
      (node (ref "P301") (pin "P$28") (pinfunction "P2-28_P$28") (pintype "bidirectional"))
    )
    (net (code "79") (name "unconnected-(P301-P2-30-PadP$30)") (class "Default")
      (node (ref "P301") (pin "P$30") (pinfunction "P2-30_P$30") (pintype "bidirectional"))
    )
    (net (code "80") (name "unconnected-(P301-P2-32-PadP$32)") (class "Default")
      (node (ref "P301") (pin "P$32") (pinfunction "P2-32_P$32") (pintype "bidirectional"))
    )
    (net (code "81") (name "unconnected-(P301-P2-34-PadP$34)") (class "Default")
      (node (ref "P301") (pin "P$34") (pinfunction "P2-34_P$34") (pintype "bidirectional"))
    )
    (net (code "82") (name "unconnected-(P301-P2-36-PadP$36)") (class "Default")
      (node (ref "P301") (pin "P$36") (pinfunction "P2-36_P$36") (pintype "bidirectional"))
    )
    (net (code "83") (name "unconnected-(P301-P2-38-PadP$38)") (class "Default")
      (node (ref "P301") (pin "P$38") (pinfunction "P2-38_P$38") (pintype "bidirectional"))
    )
    (net (code "84") (name "unconnected-(P301-P2-41-PadP$41)") (class "Default")
      (node (ref "P301") (pin "P$41") (pinfunction "P2-41_P$41") (pintype "bidirectional"))
    )
    (net (code "85") (name "unconnected-(P301-P2-42-PadP$42)") (class "Default")
      (node (ref "P301") (pin "P$42") (pinfunction "P2-42_P$42") (pintype "bidirectional"))
    )
    (net (code "86") (name "unconnected-(P301-P2-44-PadP$44)") (class "Default")
      (node (ref "P301") (pin "P$44") (pinfunction "P2-44_P$44") (pintype "bidirectional"))
    )
    (net (code "87") (name "unconnected-(P301-P2-46-PadP$46)") (class "Default")
      (node (ref "P301") (pin "P$46") (pinfunction "P2-46_P$46") (pintype "bidirectional"))
    )
    (net (code "88") (name "unconnected-(P301-P2-47-PadP$47)") (class "Default")
      (node (ref "P301") (pin "P$47") (pinfunction "P2-47_P$47") (pintype "bidirectional"))
    )
    (net (code "89") (name "unconnected-(P301-P2-48-PadP$48)") (class "Default")
      (node (ref "P301") (pin "P$48") (pinfunction "P2-48_P$48") (pintype "bidirectional"))
    )
    (net (code "90") (name "unconnected-(P301-P2-49-PadP$49)") (class "Default")
      (node (ref "P301") (pin "P$49") (pinfunction "P2-49_P$49") (pintype "bidirectional"))
    )
    (net (code "91") (name "unconnected-(P301-P2-50-PadP$50)") (class "Default")
      (node (ref "P301") (pin "P$50") (pinfunction "P2-50_P$50") (pintype "bidirectional"))
    )
    (net (code "92") (name "unconnected-(P301-P2-52-PadP$52)") (class "Default")
      (node (ref "P301") (pin "P$52") (pinfunction "P2-52_P$52") (pintype "bidirectional"))
    )
    (net (code "93") (name "unconnected-(P301-P2-54-PadP$54)") (class "Default")
      (node (ref "P301") (pin "P$54") (pinfunction "P2-54_P$54") (pintype "bidirectional"))
    )
    (net (code "94") (name "unconnected-(P301-P2-55-PadP$55)") (class "Default")
      (node (ref "P301") (pin "P$55") (pinfunction "P2-55_P$55") (pintype "bidirectional"))
    )
    (net (code "95") (name "unconnected-(P301-P2-56-PadP$56)") (class "Default")
      (node (ref "P301") (pin "P$56") (pinfunction "P2-56_P$56") (pintype "bidirectional"))
    )
    (net (code "96") (name "unconnected-(P301-P2-58-PadP$58)") (class "Default")
      (node (ref "P301") (pin "P$58") (pinfunction "P2-58_P$58") (pintype "bidirectional"))
    )
    (net (code "97") (name "unconnected-(P301-P2-67-PadP$67)") (class "Default")
      (node (ref "P301") (pin "P$67") (pinfunction "P2-67_P$67") (pintype "bidirectional"))
    )
    (net (code "98") (name "unconnected-(P301-P2-69-PadP$69)") (class "Default")
      (node (ref "P301") (pin "P$69") (pinfunction "P2-69_P$69") (pintype "bidirectional"))
    )
    (net (code "99") (name "unconnected-(P301-P3-1-PadP$71)") (class "Default")
      (node (ref "P301") (pin "P$71") (pinfunction "P3-1_P$71") (pintype "bidirectional"))
    )
    (net (code "100") (name "unconnected-(P301-P3-2-PadP$72)") (class "Default")
      (node (ref "P301") (pin "P$72") (pinfunction "P3-2_P$72") (pintype "bidirectional"))
    )
    (net (code "101") (name "unconnected-(P301-P3-3-PadP$73)") (class "Default")
      (node (ref "P301") (pin "P$73") (pinfunction "P3-3_P$73") (pintype "bidirectional"))
    )
    (net (code "102") (name "unconnected-(P301-P3-4-PadP$74)") (class "Default")
      (node (ref "P301") (pin "P$74") (pinfunction "P3-4_P$74") (pintype "bidirectional"))
    )
    (net (code "103") (name "unconnected-(P301-P3-5-PadP$75)") (class "Default")
      (node (ref "P301") (pin "P$75") (pinfunction "P3-5_P$75") (pintype "bidirectional"))
    )
    (net (code "104") (name "unconnected-(P301-P3-6-PadP$76)") (class "Default")
      (node (ref "P301") (pin "P$76") (pinfunction "P3-6_P$76") (pintype "bidirectional"))
    )
    (net (code "105") (name "unconnected-(P301-P3-7-PadP$77)") (class "Default")
      (node (ref "P301") (pin "P$77") (pinfunction "P3-7_P$77") (pintype "bidirectional"))
    )
    (net (code "106") (name "unconnected-(P301-P3-8-PadP$78)") (class "Default")
      (node (ref "P301") (pin "P$78") (pinfunction "P3-8_P$78") (pintype "bidirectional"))
    )
    (net (code "107") (name "unconnected-(P301-P3-9-PadP$79)") (class "Default")
      (node (ref "P301") (pin "P$79") (pinfunction "P3-9_P$79") (pintype "bidirectional"))
    )
    (net (code "108") (name "unconnected-(P301-P3-10-PadP$80)") (class "Default")
      (node (ref "P301") (pin "P$80") (pinfunction "P3-10_P$80") (pintype "bidirectional"))
    )
    (net (code "109") (name "unconnected-(P301-P3-11-PadP$81)") (class "Default")
      (node (ref "P301") (pin "P$81") (pinfunction "P3-11_P$81") (pintype "bidirectional"))
    )
    (net (code "110") (name "unconnected-(P301-P3-12-PadP$82)") (class "Default")
      (node (ref "P301") (pin "P$82") (pinfunction "P3-12_P$82") (pintype "bidirectional"))
    )
    (net (code "111") (name "unconnected-(P301-P3-13-PadP$83)") (class "Default")
      (node (ref "P301") (pin "P$83") (pinfunction "P3-13_P$83") (pintype "bidirectional"))
    )
    (net (code "112") (name "unconnected-(P301-P3-14-PadP$84)") (class "Default")
      (node (ref "P301") (pin "P$84") (pinfunction "P3-14_P$84") (pintype "bidirectional"))
    )
    (net (code "113") (name "unconnected-(P301-P3-15-PadP$85)") (class "Default")
      (node (ref "P301") (pin "P$85") (pinfunction "P3-15_P$85") (pintype "bidirectional"))
    )
    (net (code "114") (name "unconnected-(P301-P3-16-PadP$86)") (class "Default")
      (node (ref "P301") (pin "P$86") (pinfunction "P3-16_P$86") (pintype "bidirectional"))
    )
    (net (code "115") (name "unconnected-(P301-P3-17-PadP$87)") (class "Default")
      (node (ref "P301") (pin "P$87") (pinfunction "P3-17_P$87") (pintype "bidirectional"))
    )
    (net (code "116") (name "unconnected-(P301-P3-18-PadP$88)") (class "Default")
      (node (ref "P301") (pin "P$88") (pinfunction "P3-18_P$88") (pintype "bidirectional"))
    )
    (net (code "117") (name "unconnected-(P301-P3-19-PadP$89)") (class "Default")
      (node (ref "P301") (pin "P$89") (pinfunction "P3-19_P$89") (pintype "bidirectional"))
    )
    (net (code "118") (name "unconnected-(P301-P3-20-PadP$90)") (class "Default")
      (node (ref "P301") (pin "P$90") (pinfunction "P3-20_P$90") (pintype "bidirectional"))
    )
    (net (code "119") (name "unconnected-(P301-P3-23-PadP$93)") (class "Default")
      (node (ref "P301") (pin "P$93") (pinfunction "P3-23_P$93") (pintype "bidirectional"))
    )
    (net (code "120") (name "unconnected-(P301-P3-24-PadP$94)") (class "Default")
      (node (ref "P301") (pin "P$94") (pinfunction "P3-24_P$94") (pintype "bidirectional"))
    )
    (net (code "121") (name "unconnected-(P301-P3-25-PadP$95)") (class "Default")
      (node (ref "P301") (pin "P$95") (pinfunction "P3-25_P$95") (pintype "bidirectional"))
    )
    (net (code "122") (name "unconnected-(P301-P3-26-PadP$96)") (class "Default")
      (node (ref "P301") (pin "P$96") (pinfunction "P3-26_P$96") (pintype "bidirectional"))
    )
    (net (code "123") (name "unconnected-(P301-P3-27-PadP$97)") (class "Default")
      (node (ref "P301") (pin "P$97") (pinfunction "P3-27_P$97") (pintype "bidirectional"))
    )
    (net (code "124") (name "unconnected-(P301-P3-28-PadP$98)") (class "Default")
      (node (ref "P301") (pin "P$98") (pinfunction "P3-28_P$98") (pintype "bidirectional"))
    )
    (net (code "125") (name "unconnected-(P301-P3-29-PadP$99)") (class "Default")
      (node (ref "P301") (pin "P$99") (pinfunction "P3-29_P$99") (pintype "bidirectional"))
    )
    (net (code "126") (name "unconnected-(P301-P3-30-PadP$100)") (class "Default")
      (node (ref "P301") (pin "P$100") (pinfunction "P3-30_P$100") (pintype "bidirectional"))
    )
    (net (code "127") (name "unconnected-(P301-P3-31-PadP$101)") (class "Default")
      (node (ref "P301") (pin "P$101") (pinfunction "P3-31_P$101") (pintype "bidirectional"))
    )
    (net (code "128") (name "unconnected-(P301-P3-32-PadP$102)") (class "Default")
      (node (ref "P301") (pin "P$102") (pinfunction "P3-32_P$102") (pintype "bidirectional"))
    )
    (net (code "129") (name "unconnected-(P301-P3-33-PadP$103)") (class "Default")
      (node (ref "P301") (pin "P$103") (pinfunction "P3-33_P$103") (pintype "bidirectional"))
    )
    (net (code "130") (name "unconnected-(P301-P3-34-PadP$104)") (class "Default")
      (node (ref "P301") (pin "P$104") (pinfunction "P3-34_P$104") (pintype "bidirectional"))
    )
    (net (code "131") (name "unconnected-(P301-P3-35-PadP$105)") (class "Default")
      (node (ref "P301") (pin "P$105") (pinfunction "P3-35_P$105") (pintype "bidirectional"))
    )
    (net (code "132") (name "unconnected-(P301-P3-36-PadP$106)") (class "Default")
      (node (ref "P301") (pin "P$106") (pinfunction "P3-36_P$106") (pintype "bidirectional"))
    )
    (net (code "133") (name "unconnected-(P301-P3-37-PadP$107)") (class "Default")
      (node (ref "P301") (pin "P$107") (pinfunction "P3-37_P$107") (pintype "bidirectional"))
    )
    (net (code "134") (name "unconnected-(P301-P3-38-PadP$108)") (class "Default")
      (node (ref "P301") (pin "P$108") (pinfunction "P3-38_P$108") (pintype "bidirectional"))
    )
    (net (code "135") (name "unconnected-(P301-P3-39-PadP$109)") (class "Default")
      (node (ref "P301") (pin "P$109") (pinfunction "P3-39_P$109") (pintype "bidirectional"))
    )
    (net (code "136") (name "unconnected-(P301-P3-40-PadP$110)") (class "Default")
      (node (ref "P301") (pin "P$110") (pinfunction "P3-40_P$110") (pintype "bidirectional"))
    )
    (net (code "137") (name "unconnected-(P301-P3-41-PadP$111)") (class "Default")
      (node (ref "P301") (pin "P$111") (pinfunction "P3-41_P$111") (pintype "bidirectional"))
    )
    (net (code "138") (name "unconnected-(P301-P3-42-PadP$112)") (class "Default")
      (node (ref "P301") (pin "P$112") (pinfunction "P3-42_P$112") (pintype "bidirectional"))
    )
    (net (code "139") (name "unconnected-(P301-P3-43-PadP$113)") (class "Default")
      (node (ref "P301") (pin "P$113") (pinfunction "P3-43_P$113") (pintype "bidirectional"))
    )
    (net (code "140") (name "unconnected-(P301-P3-44-PadP$114)") (class "Default")
      (node (ref "P301") (pin "P$114") (pinfunction "P3-44_P$114") (pintype "bidirectional"))
    )
    (net (code "141") (name "unconnected-(P301-P3-45-PadP$115)") (class "Default")
      (node (ref "P301") (pin "P$115") (pinfunction "P3-45_P$115") (pintype "bidirectional"))
    )
    (net (code "142") (name "unconnected-(P301-P3-46-PadP$116)") (class "Default")
      (node (ref "P301") (pin "P$116") (pinfunction "P3-46_P$116") (pintype "bidirectional"))
    )
    (net (code "143") (name "unconnected-(P301-P3-47-PadP$117)") (class "Default")
      (node (ref "P301") (pin "P$117") (pinfunction "P3-47_P$117") (pintype "bidirectional"))
    )
    (net (code "144") (name "unconnected-(P301-P3-48-PadP$118)") (class "Default")
      (node (ref "P301") (pin "P$118") (pinfunction "P3-48_P$118") (pintype "bidirectional"))
    )
    (net (code "145") (name "unconnected-(P301-P3-49-PadP$119)") (class "Default")
      (node (ref "P301") (pin "P$119") (pinfunction "P3-49_P$119") (pintype "bidirectional"))
    )
    (net (code "146") (name "unconnected-(P301-P3-51-PadP$121)") (class "Default")
      (node (ref "P301") (pin "P$121") (pinfunction "P3-51_P$121") (pintype "bidirectional"))
    )
    (net (code "147") (name "unconnected-(P301-P3-53-PadP$123)") (class "Default")
      (node (ref "P301") (pin "P$123") (pinfunction "P3-53_P$123") (pintype "bidirectional"))
    )
    (net (code "148") (name "unconnected-(P301-P3-55-PadP$125)") (class "Default")
      (node (ref "P301") (pin "P$125") (pinfunction "P3-55_P$125") (pintype "bidirectional"))
    )
    (net (code "149") (name "unconnected-(P301-P3-56-PadP$126)") (class "Default")
      (node (ref "P301") (pin "P$126") (pinfunction "P3-56_P$126") (pintype "bidirectional"))
    )
    (net (code "150") (name "unconnected-(P301-P3-58-PadP$128)") (class "Default")
      (node (ref "P301") (pin "P$128") (pinfunction "P3-58_P$128") (pintype "bidirectional"))
    )
    (net (code "151") (name "unconnected-(P301-P3-60-PadP$130)") (class "Default")
      (node (ref "P301") (pin "P$130") (pinfunction "P3-60_P$130") (pintype "bidirectional"))
    )
    (net (code "152") (name "unconnected-(P301-P3-62-PadP$132)") (class "Default")
      (node (ref "P301") (pin "P$132") (pinfunction "P3-62_P$132") (pintype "bidirectional"))
    )
    (net (code "153") (name "unconnected-(P301-P3-63-PadP$133)") (class "Default")
      (node (ref "P301") (pin "P$133") (pinfunction "P3-63_P$133") (pintype "bidirectional"))
    )
    (net (code "154") (name "unconnected-(P301-P3-64-PadP$134)") (class "Default")
      (node (ref "P301") (pin "P$134") (pinfunction "P3-64_P$134") (pintype "bidirectional"))
    )
    (net (code "155") (name "unconnected-(P301-P3-66-PadP$136)") (class "Default")
      (node (ref "P301") (pin "P$136") (pinfunction "P3-66_P$136") (pintype "bidirectional"))
    )
    (net (code "156") (name "unconnected-(P301-P3-68-PadP$138)") (class "Default")
      (node (ref "P301") (pin "P$138") (pinfunction "P3-68_P$138") (pintype "bidirectional"))
    )
    (net (code "157") (name "unconnected-(P301-P3-70-PadP$140)") (class "Default")
      (node (ref "P301") (pin "P$140") (pinfunction "P3-70_P$140") (pintype "bidirectional"))
    )
    (net (code "158") (name "unconnected-(U$1-7{slash}EXT_IN-Pad7{slash}EXINT)") (class "Default")
      (node (ref "U$1") (pin "7/EXINT") (pinfunction "7/EXT_IN_7/EXINT") (pintype "bidirectional"))
    )
    (net (code "159") (name "unconnected-(U$1-30_ANTON-Pad30{slash}ANTON)") (class "Default")
      (node (ref "U$1") (pin "30/ANTON") (pinfunction "30_ANTON_30/ANTON") (pintype "bidirectional"))
    )
    (net (code "160") (name "unconnected-(U$1-Pad3{slash}SDA)") (class "Default")
      (node (ref "U$1") (pin "3/SDA") (pinfunction "3/SDA_3/SDA") (pintype "bidirectional"))
    )
    (net (code "161") (name "unconnected-(U$1-Pad6{slash}SCL)") (class "Default")
      (node (ref "U$1") (pin "6/SCL") (pinfunction "6/SCL_6/SCL") (pintype "bidirectional"))
    )
    (net (code "162") (name "unconnected-(U$1-Pad20{slash}DSEL)") (class "Default")
      (node (ref "U$1") (pin "20/DSEL") (pinfunction "20/DSEL_20/DSEL") (pintype "bidirectional"))
    )
    (net (code "163") (name "unconnected-(U$1-Pad29{slash}TIMEPULSE)") (class "Default")
      (node (ref "U$1") (pin "29/TIMEPULSE") (pinfunction "29/TIMEPULSE_29/TIMEPULSE") (pintype "bidirectional"))
    )
    (net (code "164") (name "unconnected-(U$2-CFG_SEL1-Pad28)") (class "Default")
      (node (ref "U$2") (pin "28") (pinfunction "CFG_SEL1_28") (pintype "bidirectional"))
    )
    (net (code "165") (name "unconnected-(U$2-NC-Pad19)") (class "Default")
      (node (ref "U$2") (pin "19") (pinfunction "NC_19") (pintype "bidirectional"))
    )
    (net (code "166") (name "unconnected-(U$2-NC-Pad22)") (class "Default")
      (node (ref "U$2") (pin "22") (pinfunction "NC_22") (pintype "bidirectional"))
    )
    (net (code "167") (name "unconnected-(U$2-NC-Pad23)") (class "Default")
      (node (ref "U$2") (pin "23") (pinfunction "NC_23") (pintype "bidirectional"))
    )
    (net (code "168") (name "unconnected-(U$2-NC-Pad24)") (class "Default")
      (node (ref "U$2") (pin "24") (pinfunction "NC_24") (pintype "bidirectional"))
    )
    (net (code "169") (name "unconnected-(U$2-NC-Pad25)") (class "Default")
      (node (ref "U$2") (pin "25") (pinfunction "NC_25") (pintype "bidirectional"))
    )
    (net (code "170") (name "unconnected-(U$2-NC-Pad36)") (class "Default")
      (node (ref "U$2") (pin "36") (pinfunction "NC_36") (pintype "bidirectional"))
    )
    (net (code "171") (name "unconnected-(U$2-TEST-Pad30)") (class "Default")
      (node (ref "U$2") (pin "30") (pinfunction "TEST_30") (pintype "bidirectional"))
    )
    (net (code "172") (name "unconnected-(U2-AD0-Pad9)") (class "Default")
      (node (ref "U2") (pin "9") (pinfunction "AD0_9") (pintype "bidirectional"))
    )
    (net (code "173") (name "unconnected-(U2-CLKIN-Pad1)") (class "Default")
      (node (ref "U2") (pin "1") (pinfunction "CLKIN_1") (pintype "bidirectional"))
    )
    (net (code "174") (name "unconnected-(U2-CLKOUT-Pad22)") (class "Default")
      (node (ref "U2") (pin "22") (pinfunction "CLKOUT_22") (pintype "bidirectional"))
    )
    (net (code "175") (name "unconnected-(U2-E_SCL-Pad7)") (class "Default")
      (node (ref "U2") (pin "7") (pinfunction "E_SCL_7") (pintype "bidirectional"))
    )
    (net (code "176") (name "unconnected-(U2-E_SDA-Pad6)") (class "Default")
      (node (ref "U2") (pin "6") (pinfunction "E_SDA_6") (pintype "bidirectional"))
    )
    (net (code "177") (name "unconnected-(U2-FSYNC-Pad11)") (class "Default")
      (node (ref "U2") (pin "11") (pinfunction "FSYNC_11") (pintype "bidirectional"))
    )
  )
)
